# Adafruit_Mini_Analog_Thumbstick.net
KiCad netlist of a schematic drawn in EAGLE
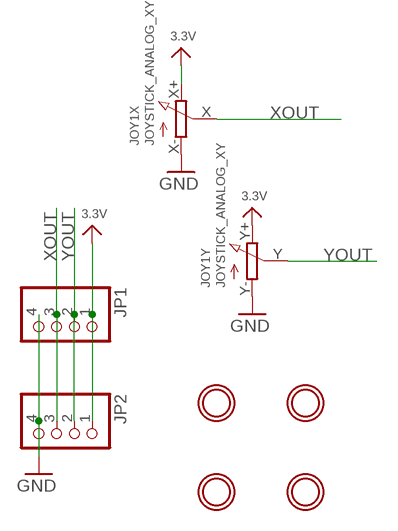
[diagram p0: schematic, sheet 1]

(export (version "E")
  (design (tool "Eeschema 10.0.6"))
  (components
    (comp (ref "JOY1")
      (value "JOYSTICK_ANALOG_XY")
      (footprint "eagle-import:JOYSTICK_ANALOG_MINITHM")
      (libsource (lib "eagle-import") (part "JOYSTICK_ANALOG_XY"))
    )
    (comp (ref "JP1")
      (value "HEADER-1X476MIL")
      (footprint "eagle-import:1X04_ROUND_76")
      (libsource (lib "eagle-import") (part "HEADER-1X476MIL"))
    )
    (comp (ref "JP2")
      (value "HEADER-1X476MIL")
      (footprint "eagle-import:1X04_ROUND_76")
      (libsource (lib "eagle-import") (part "HEADER-1X476MIL"))
    )
    (comp (ref "U$1")
      (value "MOUNTINGHOLE2.0")
      (footprint "eagle-import:MOUNTINGHOLE_2.0_PLATED")
      (libsource (lib "eagle-import") (part "MOUNTINGHOLE2.0"))
    )
    (comp (ref "U$4")
      (value "MOUNTINGHOLE2.0")
      (footprint "eagle-import:MOUNTINGHOLE_2.0_PLATED")
      (libsource (lib "eagle-import") (part "MOUNTINGHOLE2.0"))
    )
    (comp (ref "U$5")
      (value "MOUNTINGHOLE2.0")
      (footprint "eagle-import:MOUNTINGHOLE_2.0_PLATED")
      (libsource (lib "eagle-import") (part "MOUNTINGHOLE2.0"))
    )
    (comp (ref "U$6")
      (value "MOUNTINGHOLE2.0")
      (footprint "eagle-import:MOUNTINGHOLE_2.0_PLATED")
      (libsource (lib "eagle-import") (part "MOUNTINGHOLE2.0"))
    )
  )
  (nets
    (net (code "1") (name "/XOUT") (class "Default")
      (node (ref "JOY1") (pin "X") (pinfunction "S_X") (pintype "passive"))
      (node (ref "JP1") (pin "3") (pinfunction "3_3") (pintype "passive"))
      (node (ref "JP2") (pin "3") (pinfunction "3_3") (pintype "passive"))
    )
    (net (code "2") (name "/YOUT") (class "Default")
      (node (ref "JOY1") (pin "Y") (pinfunction "S_Y") (pintype "passive"))
      (node (ref "JP1") (pin "2") (pinfunction "2_2") (pintype "passive"))
      (node (ref "JP2") (pin "2") (pinfunction "2_2") (pintype "passive"))
    )
    (net (code "3") (name "3.3V") (class "Default")
      (node (ref "JOY1") (pin "X+") (pinfunction "E_X+") (pintype "passive"))
      (node (ref "JOY1") (pin "Y+") (pinfunction "E_Y+") (pintype "passive"))
      (node (ref "JP1") (pin "1") (pinfunction "1_1") (pintype "passive"))
      (node (ref "JP2") (pin "1") (pinfunction "1_1") (pintype "passive"))
    )
    (net (code "4") (name "GND") (class "Default")
      (node (ref "JOY1") (pin "X-") (pinfunction "A_X-") (pintype "passive"))
      (node (ref "JOY1") (pin "Y-") (pinfunction "A_Y-") (pintype "passive"))
      (node (ref "JP1") (pin "4") (pinfunction "4_4") (pintype "passive"))
      (node (ref "JP2") (pin "4") (pinfunction "4_4") (pintype "passive"))
    )
  )
)
